# ET-IO.net
KiCad netlist of a schematic drawn in Altium Designer
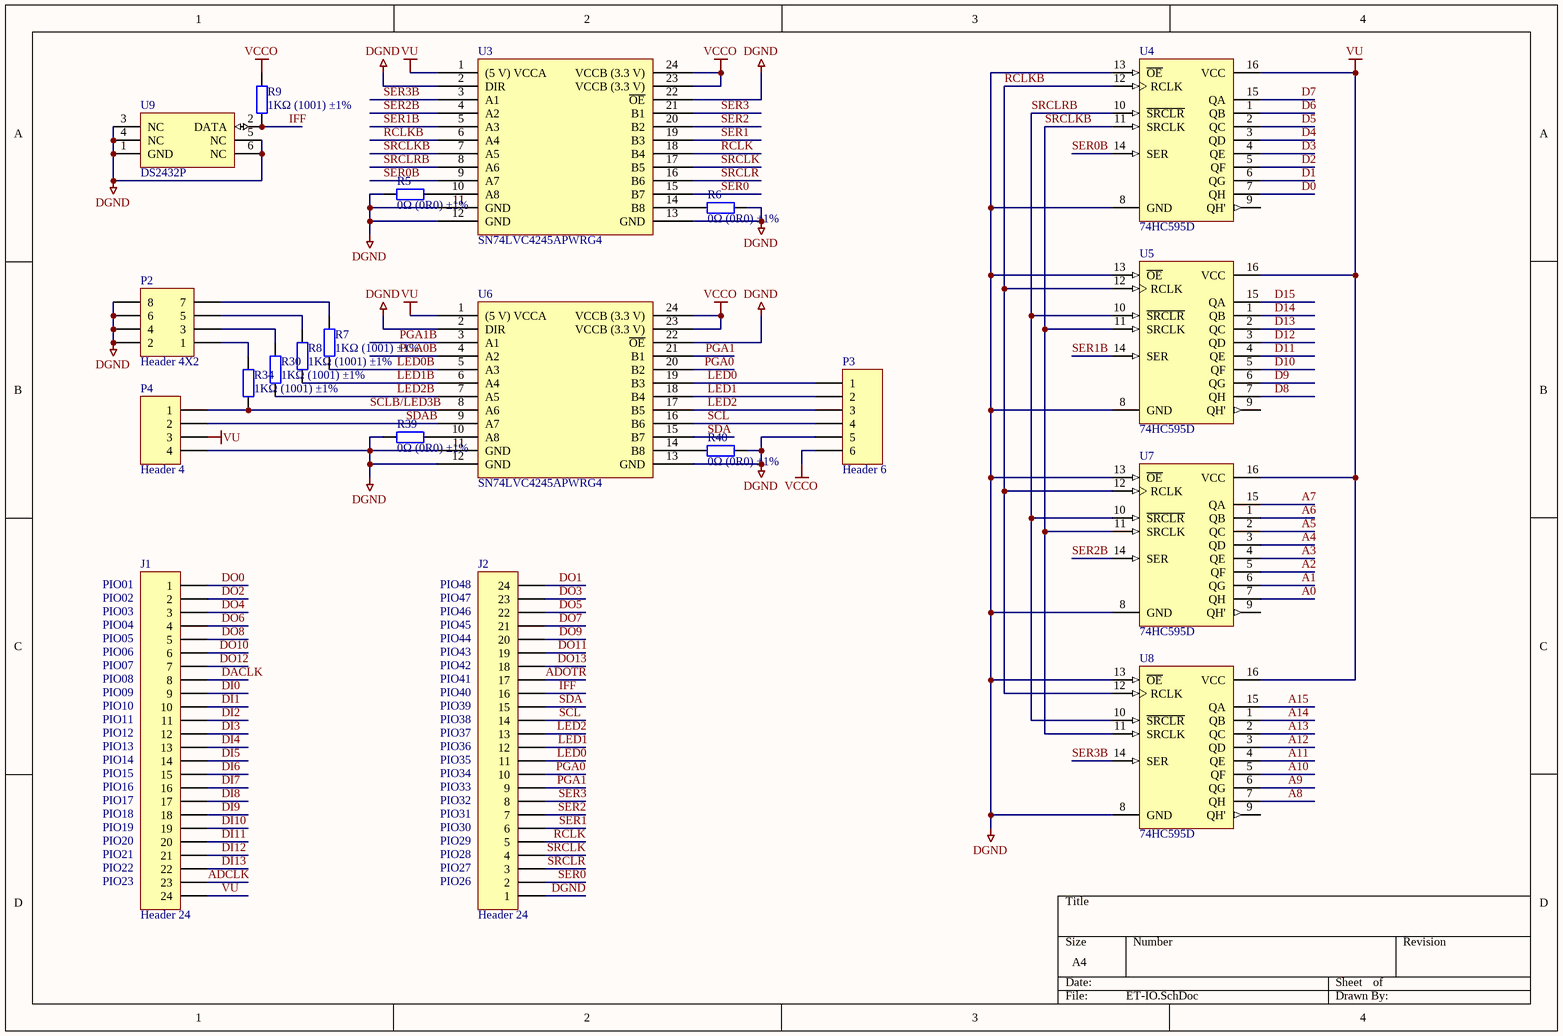
[diagram p0: ET-IO.SchDoc]

(export (version "E")
  (design (tool "Eeschema 10.0.6"))
  (components
    (comp (ref "J1")
      (value "Header 24")
      (footprint "HDR1X24")
      (description "Header, 24-Pin")
      (fields (field (name "PUBLISHER") "Altium Limited"))
      (libsource (lib "") (part "Header 24_1"))
    )
    (comp (ref "J2")
      (value "Header 24")
      (footprint "HDR1X24")
      (description "Header, 24-Pin")
      (fields (field (name "PUBLISHER") "Altium Limited"))
      (libsource (lib "Miscellaneous Connectors") (part "Header 24"))
    )
    (comp (ref "P2")
      (value "Header 4X2")
      (footprint "HDR2X4")
      (description "Header, 4-Pin, Dual row")
      (fields (field (name "PUBLISHER") "Altium Limited"))
      (libsource (lib "Miscellaneous Connectors") (part "Header 4X2"))
    )
    (comp (ref "P3")
      (value "Header 6")
      (footprint "HDR1X6")
      (description "Header, 6-Pin")
      (fields (field (name "PUBLISHER") "Altium Limited"))
      (libsource (lib "Miscellaneous Connectors") (part "Header 6"))
    )
    (comp (ref "P4")
      (value "Header 4")
      (footprint "HDR1X4")
      (description "Header, 4-Pin")
      (fields (field (name "PUBLISHER") "Altium Limited"))
      (libsource (lib "Miscellaneous Connectors") (part "Header 4"))
    )
    (comp (ref "R5")
      (value "0Ω (0R0) ±1%")
      (footprint "LC-0805_R")
      (description "贴片电阻")
      (libsource (lib "Miscellaneous Devices LC") (part "0805 0Ω (0R0) 1%"))
    )
    (comp (ref "R6")
      (value "0Ω (0R0) ±1%")
      (footprint "LC-0805_R")
      (description "贴片电阻")
      (libsource (lib "Miscellaneous Devices LC") (part "0805 0Ω (0R0) 1%"))
    )
    (comp (ref "R7")
      (value "1KΩ (1001) ±1%")
      (footprint "LC-0805_R")
      (description "贴片电阻")
      (libsource (lib "Miscellaneous Devices LC") (part "0805 1KΩ (1001) 1%"))
    )
    (comp (ref "R8")
      (value "1KΩ (1001) ±1%")
      (footprint "LC-0805_R")
      (description "贴片电阻")
      (libsource (lib "Miscellaneous Devices LC") (part "0805 1KΩ (1001) 1%"))
    )
    (comp (ref "R9")
      (value "1KΩ (1001) ±1%")
      (footprint "LC-0805_R")
      (description "贴片电阻")
      (libsource (lib "Miscellaneous Devices LC") (part "0805 1KΩ (1001) 1%"))
    )
    (comp (ref "R30")
      (value "1KΩ (1001) ±1%")
      (footprint "LC-0805_R")
      (description "贴片电阻")
      (libsource (lib "") (part "0805 1KΩ (1001) 1%_1"))
    )
    (comp (ref "R34")
      (value "1KΩ (1001) ±1%")
      (footprint "LC-0805_R")
      (description "贴片电阻")
      (libsource (lib "Miscellaneous Devices LC") (part "0805 1KΩ (1001) 1%"))
    )
    (comp (ref "R39")
      (value "0Ω (0R0) ±1%")
      (footprint "LC-0805_R")
      (description "贴片电阻")
      (libsource (lib "Miscellaneous Devices LC") (part "0805 0Ω (0R0) 1%"))
    )
    (comp (ref "R40")
      (value "0Ω (0R0) ±1%")
      (footprint "LC-0805_R")
      (description "贴片电阻")
      (libsource (lib "Miscellaneous Devices LC") (part "0805 0Ω (0R0) 1%"))
    )
    (comp (ref "U3")
      (value "SN74LVC4245APWRG4")
      (footprint "LC-TSSOP-24")
      (description "74系列逻辑芯片")
      (libsource (lib "Miscellaneous Devices LC") (part "SN74LVC4245APWRG4"))
    )
    (comp (ref "U4")
      (value "74HC595D")
      (footprint "LC-SOIC-16_150mil")
      (description "74系列逻辑芯片")
      (libsource (lib "Miscellaneous Devices LC") (part "74HC595D"))
    )
    (comp (ref "U5")
      (value "74HC595D")
      (footprint "LC-SOIC-16_150mil")
      (description "74系列逻辑芯片")
      (libsource (lib "Miscellaneous Devices LC") (part "74HC595D"))
    )
    (comp (ref "U6")
      (value "SN74LVC4245APWRG4")
      (footprint "LC-TSSOP-24")
      (description "74系列逻辑芯片")
      (libsource (lib "Miscellaneous Devices LC") (part "SN74LVC4245APWRG4"))
    )
    (comp (ref "U7")
      (value "74HC595D")
      (footprint "LC-SOIC-16_150mil")
      (description "74系列逻辑芯片")
      (libsource (lib "Miscellaneous Devices LC") (part "74HC595D"))
    )
    (comp (ref "U8")
      (value "74HC595D")
      (footprint "LC-SOIC-16_150mil")
      (description "74系列逻辑芯片")
      (libsource (lib "Miscellaneous Devices LC") (part "74HC595D"))
    )
    (comp (ref "U9")
      (value "DS2432P")
      (footprint "mini-ET:TSOC6")
      (description "256-Bit 1-Wire EEPROM")
      (fields (field (name "PUBLISHER") "Altium Limited"))
      (libsource (lib "Dallas Memory EEPROM") (part "DS2430AP"))
    )
  )
  (nets
    (net (code "1") (name "/A0") (class "Default")
      (node (ref "U7") (pin "7") (pinfunction "QH_7") (pintype "tri_state"))
    )
    (net (code "2") (name "/A1") (class "Default")
      (node (ref "U7") (pin "6") (pinfunction "QG_6") (pintype "tri_state"))
    )
    (net (code "3") (name "/A2") (class "Default")
      (node (ref "U7") (pin "5") (pinfunction "QF_5") (pintype "tri_state"))
    )
    (net (code "4") (name "/A3") (class "Default")
      (node (ref "U7") (pin "4") (pinfunction "QE_4") (pintype "tri_state"))
    )
    (net (code "5") (name "/A4") (class "Default")
      (node (ref "U7") (pin "3") (pinfunction "QD_3") (pintype "tri_state"))
    )
    (net (code "6") (name "/A5") (class "Default")
      (node (ref "U7") (pin "2") (pinfunction "QC_2") (pintype "tri_state"))
    )
    (net (code "7") (name "/A6") (class "Default")
      (node (ref "U7") (pin "1") (pinfunction "QB_1") (pintype "tri_state"))
    )
    (net (code "8") (name "/A7") (class "Default")
      (node (ref "U7") (pin "15") (pinfunction "QA_15") (pintype "tri_state"))
    )
    (net (code "9") (name "/A8") (class "Default")
      (node (ref "U8") (pin "7") (pinfunction "QH_7") (pintype "tri_state"))
    )
    (net (code "10") (name "/A9") (class "Default")
      (node (ref "U8") (pin "6") (pinfunction "QG_6") (pintype "tri_state"))
    )
    (net (code "11") (name "/A10") (class "Default")
      (node (ref "U8") (pin "5") (pinfunction "QF_5") (pintype "tri_state"))
    )
    (net (code "12") (name "/A11") (class "Default")
      (node (ref "U8") (pin "4") (pinfunction "QE_4") (pintype "tri_state"))
    )
    (net (code "13") (name "/A12") (class "Default")
      (node (ref "U8") (pin "3") (pinfunction "QD_3") (pintype "tri_state"))
    )
    (net (code "14") (name "/A13") (class "Default")
      (node (ref "U8") (pin "2") (pinfunction "QC_2") (pintype "tri_state"))
    )
    (net (code "15") (name "/A14") (class "Default")
      (node (ref "U8") (pin "1") (pinfunction "QB_1") (pintype "tri_state"))
    )
    (net (code "16") (name "/A15") (class "Default")
      (node (ref "U8") (pin "15") (pinfunction "QA_15") (pintype "tri_state"))
    )
    (net (code "17") (name "/ADCLK") (class "Default")
      (node (ref "J1") (pin "23") (pinfunction "23_23") (pintype "passive"))
    )
    (net (code "18") (name "/ADOTR") (class "Default")
      (node (ref "J2") (pin "17") (pinfunction "17_17") (pintype "passive"))
    )
    (net (code "19") (name "/D0") (class "Default")
      (node (ref "U4") (pin "7") (pinfunction "QH_7") (pintype "tri_state"))
    )
    (net (code "20") (name "/D1") (class "Default")
      (node (ref "U4") (pin "6") (pinfunction "QG_6") (pintype "tri_state"))
    )
    (net (code "21") (name "/D2") (class "Default")
      (node (ref "U4") (pin "5") (pinfunction "QF_5") (pintype "tri_state"))
    )
    (net (code "22") (name "/D3") (class "Default")
      (node (ref "U4") (pin "4") (pinfunction "QE_4") (pintype "tri_state"))
    )
    (net (code "23") (name "/D4") (class "Default")
      (node (ref "U4") (pin "3") (pinfunction "QD_3") (pintype "tri_state"))
    )
    (net (code "24") (name "/D5") (class "Default")
      (node (ref "U4") (pin "2") (pinfunction "QC_2") (pintype "tri_state"))
    )
    (net (code "25") (name "/D6") (class "Default")
      (node (ref "U4") (pin "1") (pinfunction "QB_1") (pintype "tri_state"))
    )
    (net (code "26") (name "/D7") (class "Default")
      (node (ref "U4") (pin "15") (pinfunction "QA_15") (pintype "tri_state"))
    )
    (net (code "27") (name "/D8") (class "Default")
      (node (ref "U5") (pin "7") (pinfunction "QH_7") (pintype "tri_state"))
    )
    (net (code "28") (name "/D9") (class "Default")
      (node (ref "U5") (pin "6") (pinfunction "QG_6") (pintype "tri_state"))
    )
    (net (code "29") (name "/D10") (class "Default")
      (node (ref "U5") (pin "5") (pinfunction "QF_5") (pintype "tri_state"))
    )
    (net (code "30") (name "/D11") (class "Default")
      (node (ref "U5") (pin "4") (pinfunction "QE_4") (pintype "tri_state"))
    )
    (net (code "31") (name "/D12") (class "Default")
      (node (ref "U5") (pin "3") (pinfunction "QD_3") (pintype "tri_state"))
    )
    (net (code "32") (name "/D13") (class "Default")
      (node (ref "U5") (pin "2") (pinfunction "QC_2") (pintype "tri_state"))
    )
    (net (code "33") (name "/D14") (class "Default")
      (node (ref "U5") (pin "1") (pinfunction "QB_1") (pintype "tri_state"))
    )
    (net (code "34") (name "/D15") (class "Default")
      (node (ref "U5") (pin "15") (pinfunction "QA_15") (pintype "tri_state"))
    )
    (net (code "35") (name "/DACLK") (class "Default")
      (node (ref "J1") (pin "8") (pinfunction "8_8") (pintype "passive"))
    )
    (net (code "36") (name "/DI0") (class "Default")
      (node (ref "J1") (pin "9") (pinfunction "9_9") (pintype "passive"))
    )
    (net (code "37") (name "/DI1") (class "Default")
      (node (ref "J1") (pin "10") (pinfunction "10_10") (pintype "passive"))
    )
    (net (code "38") (name "/DI2") (class "Default")
      (node (ref "J1") (pin "11") (pinfunction "11_11") (pintype "passive"))
    )
    (net (code "39") (name "/DI3") (class "Default")
      (node (ref "J1") (pin "12") (pinfunction "12_12") (pintype "passive"))
    )
    (net (code "40") (name "/DI4") (class "Default")
      (node (ref "J1") (pin "13") (pinfunction "13_13") (pintype "passive"))
    )
    (net (code "41") (name "/DI5") (class "Default")
      (node (ref "J1") (pin "14") (pinfunction "14_14") (pintype "passive"))
    )
    (net (code "42") (name "/DI6") (class "Default")
      (node (ref "J1") (pin "15") (pinfunction "15_15") (pintype "passive"))
    )
    (net (code "43") (name "/DI7") (class "Default")
      (node (ref "J1") (pin "16") (pinfunction "16_16") (pintype "passive"))
    )
    (net (code "44") (name "/DI8") (class "Default")
      (node (ref "J1") (pin "17") (pinfunction "17_17") (pintype "passive"))
    )
    (net (code "45") (name "/DI9") (class "Default")
      (node (ref "J1") (pin "18") (pinfunction "18_18") (pintype "passive"))
    )
    (net (code "46") (name "/DI10") (class "Default")
      (node (ref "J1") (pin "19") (pinfunction "19_19") (pintype "passive"))
    )
    (net (code "47") (name "/DI11") (class "Default")
      (node (ref "J1") (pin "20") (pinfunction "20_20") (pintype "passive"))
    )
    (net (code "48") (name "/DI12") (class "Default")
      (node (ref "J1") (pin "21") (pinfunction "21_21") (pintype "passive"))
    )
    (net (code "49") (name "/DI13") (class "Default")
      (node (ref "J1") (pin "22") (pinfunction "22_22") (pintype "passive"))
    )
    (net (code "50") (name "/DO0") (class "Default")
      (node (ref "J1") (pin "1") (pinfunction "1_1") (pintype "passive"))
    )
    (net (code "51") (name "/DO1") (class "Default")
      (node (ref "J2") (pin "24") (pinfunction "24_24") (pintype "passive"))
    )
    (net (code "52") (name "/DO2") (class "Default")
      (node (ref "J1") (pin "2") (pinfunction "2_2") (pintype "passive"))
    )
    (net (code "53") (name "/DO3") (class "Default")
      (node (ref "J2") (pin "23") (pinfunction "23_23") (pintype "passive"))
    )
    (net (code "54") (name "/DO4") (class "Default")
      (node (ref "J1") (pin "3") (pinfunction "3_3") (pintype "passive"))
    )
    (net (code "55") (name "/DO5") (class "Default")
      (node (ref "J2") (pin "22") (pinfunction "22_22") (pintype "passive"))
    )
    (net (code "56") (name "/DO6") (class "Default")
      (node (ref "J1") (pin "4") (pinfunction "4_4") (pintype "passive"))
    )
    (net (code "57") (name "/DO7") (class "Default")
      (node (ref "J2") (pin "21") (pinfunction "21_21") (pintype "passive"))
    )
    (net (code "58") (name "/DO8") (class "Default")
      (node (ref "J1") (pin "5") (pinfunction "5_5") (pintype "passive"))
    )
    (net (code "59") (name "/DO9") (class "Default")
      (node (ref "J2") (pin "20") (pinfunction "20_20") (pintype "passive"))
    )
    (net (code "60") (name "/DO10") (class "Default")
      (node (ref "J1") (pin "6") (pinfunction "6_6") (pintype "passive"))
    )
    (net (code "61") (name "/DO11") (class "Default")
      (node (ref "J2") (pin "19") (pinfunction "19_19") (pintype "passive"))
    )
    (net (code "62") (name "/DO12") (class "Default")
      (node (ref "J1") (pin "7") (pinfunction "7_7") (pintype "passive"))
    )
    (net (code "63") (name "/DO13") (class "Default")
      (node (ref "J2") (pin "18") (pinfunction "18_18") (pintype "passive"))
    )
    (net (code "64") (name "/IFF") (class "Default")
      (node (ref "J2") (pin "16") (pinfunction "16_16") (pintype "passive"))
      (node (ref "R9") (pin "2") (pinfunction "2_2") (pintype "passive"))
      (node (ref "U9") (pin "2") (pinfunction "DATA_2") (pintype "bidirectional"))
    )
    (net (code "65") (name "/LED0") (class "Default")
      (node (ref "J2") (pin "11") (pinfunction "11_11") (pintype "passive"))
      (node (ref "P3") (pin "1") (pinfunction "1_1") (pintype "passive"))
      (node (ref "U6") (pin "19") (pinfunction "B3_19") (pintype "passive"))
    )
    (net (code "66") (name "/LED0B") (class "Default")
      (node (ref "R7") (pin "2") (pinfunction "2_2") (pintype "passive"))
      (node (ref "U6") (pin "5") (pinfunction "A3_5") (pintype "passive"))
    )
    (net (code "67") (name "/LED1") (class "Default")
      (node (ref "J2") (pin "12") (pinfunction "12_12") (pintype "passive"))
      (node (ref "P3") (pin "2") (pinfunction "2_2") (pintype "passive"))
      (node (ref "U6") (pin "18") (pinfunction "B4_18") (pintype "passive"))
    )
    (net (code "68") (name "/LED1B") (class "Default")
      (node (ref "R8") (pin "2") (pinfunction "2_2") (pintype "passive"))
      (node (ref "U6") (pin "6") (pinfunction "A4_6") (pintype "passive"))
    )
    (net (code "69") (name "/LED2") (class "Default")
      (node (ref "J2") (pin "13") (pinfunction "13_13") (pintype "passive"))
      (node (ref "P3") (pin "3") (pinfunction "3_3") (pintype "passive"))
      (node (ref "U6") (pin "17") (pinfunction "B5_17") (pintype "passive"))
    )
    (net (code "70") (name "/LED2B") (class "Default")
      (node (ref "R30") (pin "1") (pinfunction "1_1") (pintype "passive"))
      (node (ref "U6") (pin "7") (pinfunction "A5_7") (pintype "passive"))
    )
    (net (code "71") (name "/PGA0") (class "Default")
      (node (ref "J2") (pin "10") (pinfunction "10_10") (pintype "passive"))
      (node (ref "U6") (pin "20") (pinfunction "B2_20") (pintype "passive"))
    )
    (net (code "72") (name "/PGA0B") (class "Default")
      (node (ref "U6") (pin "4") (pinfunction "A2_4") (pintype "passive"))
    )
    (net (code "73") (name "/PGA1") (class "Default")
      (node (ref "J2") (pin "9") (pinfunction "9_9") (pintype "passive"))
      (node (ref "U6") (pin "21") (pinfunction "B1_21") (pintype "passive"))
    )
    (net (code "74") (name "/PGA1B") (class "Default")
      (node (ref "U6") (pin "3") (pinfunction "A1_3") (pintype "passive"))
    )
    (net (code "75") (name "/RCLK") (class "Default")
      (node (ref "J2") (pin "5") (pinfunction "5_5") (pintype "passive"))
      (node (ref "U3") (pin "18") (pinfunction "B4_18") (pintype "passive"))
    )
    (net (code "76") (name "/RCLKB") (class "Default")
      (node (ref "U3") (pin "6") (pinfunction "A4_6") (pintype "passive"))
      (node (ref "U4") (pin "12") (pinfunction "RCLK_12") (pintype "input"))
      (node (ref "U5") (pin "12") (pinfunction "RCLK_12") (pintype "input"))
      (node (ref "U7") (pin "12") (pinfunction "RCLK_12") (pintype "input"))
      (node (ref "U8") (pin "12") (pinfunction "RCLK_12") (pintype "input"))
    )
    (net (code "77") (name "/SCL") (class "Default")
      (node (ref "J2") (pin "14") (pinfunction "14_14") (pintype "passive"))
      (node (ref "P3") (pin "4") (pinfunction "4_4") (pintype "passive"))
      (node (ref "U6") (pin "16") (pinfunction "B6_16") (pintype "passive"))
    )
    (net (code "78") (name "/SCLB{slash}LED3B") (class "Default")
      (node (ref "P4") (pin "1") (pinfunction "1_1") (pintype "passive"))
      (node (ref "R34") (pin "2") (pinfunction "2_2") (pintype "passive"))
      (node (ref "U6") (pin "8") (pinfunction "A6_8") (pintype "passive"))
    )
    (net (code "79") (name "/SDA") (class "Default")
      (node (ref "J2") (pin "15") (pinfunction "15_15") (pintype "passive"))
      (node (ref "U6") (pin "15") (pinfunction "B7_15") (pintype "passive"))
    )
    (net (code "80") (name "/SDAB") (class "Default")
      (node (ref "P4") (pin "2") (pinfunction "2_2") (pintype "passive"))
      (node (ref "U6") (pin "9") (pinfunction "A7_9") (pintype "passive"))
    )
    (net (code "81") (name "/SER0") (class "Default")
      (node (ref "J2") (pin "2") (pinfunction "2_2") (pintype "passive"))
      (node (ref "U3") (pin "15") (pinfunction "B7_15") (pintype "passive"))
    )
    (net (code "82") (name "/SER0B") (class "Default")
      (node (ref "U3") (pin "9") (pinfunction "A7_9") (pintype "passive"))
      (node (ref "U4") (pin "14") (pinfunction "SER_14") (pintype "input"))
    )
    (net (code "83") (name "/SER1") (class "Default")
      (node (ref "J2") (pin "6") (pinfunction "6_6") (pintype "passive"))
      (node (ref "U3") (pin "19") (pinfunction "B3_19") (pintype "passive"))
    )
    (net (code "84") (name "/SER1B") (class "Default")
      (node (ref "U3") (pin "5") (pinfunction "A3_5") (pintype "passive"))
      (node (ref "U5") (pin "14") (pinfunction "SER_14") (pintype "input"))
    )
    (net (code "85") (name "/SER2") (class "Default")
      (node (ref "J2") (pin "7") (pinfunction "7_7") (pintype "passive"))
      (node (ref "U3") (pin "20") (pinfunction "B2_20") (pintype "passive"))
    )
    (net (code "86") (name "/SER2B") (class "Default")
      (node (ref "U3") (pin "4") (pinfunction "A2_4") (pintype "passive"))
      (node (ref "U7") (pin "14") (pinfunction "SER_14") (pintype "input"))
    )
    (net (code "87") (name "/SER3") (class "Default")
      (node (ref "J2") (pin "8") (pinfunction "8_8") (pintype "passive"))
      (node (ref "U3") (pin "21") (pinfunction "B1_21") (pintype "passive"))
    )
    (net (code "88") (name "/SER3B") (class "Default")
      (node (ref "U3") (pin "3") (pinfunction "A1_3") (pintype "passive"))
      (node (ref "U8") (pin "14") (pinfunction "SER_14") (pintype "input"))
    )
    (net (code "89") (name "/SRCLK") (class "Default")
      (node (ref "J2") (pin "4") (pinfunction "4_4") (pintype "passive"))
      (node (ref "U3") (pin "17") (pinfunction "B5_17") (pintype "passive"))
    )
    (net (code "90") (name "/SRCLKB") (class "Default")
      (node (ref "U3") (pin "7") (pinfunction "A5_7") (pintype "passive"))
      (node (ref "U4") (pin "11") (pinfunction "SRCLK_11") (pintype "input"))
      (node (ref "U5") (pin "11") (pinfunction "SRCLK_11") (pintype "input"))
      (node (ref "U7") (pin "11") (pinfunction "SRCLK_11") (pintype "input"))
      (node (ref "U8") (pin "11") (pinfunction "SRCLK_11") (pintype "input"))
    )
    (net (code "91") (name "/SRCLR") (class "Default")
      (node (ref "J2") (pin "3") (pinfunction "3_3") (pintype "passive"))
      (node (ref "U3") (pin "16") (pinfunction "B6_16") (pintype "passive"))
    )
    (net (code "92") (name "/SRCLRB") (class "Default")
      (node (ref "U3") (pin "8") (pinfunction "A6_8") (pintype "passive"))
      (node (ref "U4") (pin "10") (pinfunction "~{SRCLR}_10") (pintype "input"))
      (node (ref "U5") (pin "10") (pinfunction "~{SRCLR}_10") (pintype "input"))
      (node (ref "U7") (pin "10") (pinfunction "~{SRCLR}_10") (pintype "input"))
      (node (ref "U8") (pin "10") (pinfunction "~{SRCLR}_10") (pintype "input"))
    )
    (net (code "93") (name "DGND") (class "Default")
      (node (ref "J2") (pin "1") (pinfunction "1_1") (pintype "passive"))
      (node (ref "P2") (pin "2") (pinfunction "2_2") (pintype "passive"))
      (node (ref "P2") (pin "4") (pinfunction "4_4") (pintype "passive"))
      (node (ref "P2") (pin "6") (pinfunction "6_6") (pintype "passive"))
      (node (ref "P2") (pin "8") (pinfunction "8_8") (pintype "passive"))
      (node (ref "P3") (pin "5") (pinfunction "5_5") (pintype "passive"))
      (node (ref "P4") (pin "4") (pinfunction "4_4") (pintype "passive"))
      (node (ref "R39") (pin "1") (pinfunction "1_1") (pintype "passive"))
      (node (ref "R40") (pin "2") (pinfunction "2_2") (pintype "passive"))
      (node (ref "R5") (pin "1") (pinfunction "1_1") (pintype "passive"))
      (node (ref "R6") (pin "2") (pinfunction "2_2") (pintype "passive"))
      (node (ref "U3") (pin "11") (pinfunction "GND_11") (pintype "passive"))
      (node (ref "U3") (pin "12") (pinfunction "GND_12") (pintype "passive"))
      (node (ref "U3") (pin "13") (pinfunction "GND_13") (pintype "passive"))
      (node (ref "U3") (pin "2") (pinfunction "DIR_2") (pintype "passive"))
      (node (ref "U3") (pin "22") (pinfunction "~{OE}_22") (pintype "passive"))
      (node (ref "U4") (pin "13") (pinfunction "~{OE}_13") (pintype "input"))
      (node (ref "U4") (pin "8") (pinfunction "GND_8") (pintype "power_in"))
      (node (ref "U5") (pin "13") (pinfunction "~{OE}_13") (pintype "input"))
      (node (ref "U5") (pin "8") (pinfunction "GND_8") (pintype "power_in"))
      (node (ref "U6") (pin "11") (pinfunction "GND_11") (pintype "passive"))
      (node (ref "U6") (pin "12") (pinfunction "GND_12") (pintype "passive"))
      (node (ref "U6") (pin "13") (pinfunction "GND_13") (pintype "passive"))
      (node (ref "U6") (pin "2") (pinfunction "DIR_2") (pintype "passive"))
      (node (ref "U6") (pin "22") (pinfunction "~{OE}_22") (pintype "passive"))
      (node (ref "U7") (pin "13") (pinfunction "~{OE}_13") (pintype "input"))
      (node (ref "U7") (pin "8") (pinfunction "GND_8") (pintype "power_in"))
      (node (ref "U8") (pin "13") (pinfunction "~{OE}_13") (pintype "input"))
      (node (ref "U8") (pin "8") (pinfunction "GND_8") (pintype "power_in"))
      (node (ref "U9") (pin "1") (pinfunction "GND_1") (pintype "power_in"))
      (node (ref "U9") (pin "3") (pinfunction "NC_3") (pintype "passive"))
      (node (ref "U9") (pin "4") (pinfunction "NC_4") (pintype "passive"))
      (node (ref "U9") (pin "5") (pinfunction "NC_5") (pintype "passive"))
      (node (ref "U9") (pin "6") (pinfunction "NC_6") (pintype "passive"))
    )
    (net (code "94") (name "Net-(P2-Pad1)") (class "Default")
      (node (ref "P2") (pin "1") (pinfunction "1_1") (pintype "passive"))
      (node (ref "R34") (pin "1") (pinfunction "1_1") (pintype "passive"))
    )
    (net (code "95") (name "Net-(P2-Pad3)") (class "Default")
      (node (ref "P2") (pin "3") (pinfunction "3_3") (pintype "passive"))
      (node (ref "R30") (pin "2") (pinfunction "2_2") (pintype "passive"))
    )
    (net (code "96") (name "Net-(P2-Pad5)") (class "Default")
      (node (ref "P2") (pin "5") (pinfunction "5_5") (pintype "passive"))
      (node (ref "R8") (pin "1") (pinfunction "1_1") (pintype "passive"))
    )
    (net (code "97") (name "Net-(P2-Pad7)") (class "Default")
      (node (ref "P2") (pin "7") (pinfunction "7_7") (pintype "passive"))
      (node (ref "R7") (pin "1") (pinfunction "1_1") (pintype "passive"))
    )
    (net (code "98") (name "Net-(U3-A8)") (class "Default")
      (node (ref "R5") (pin "2") (pinfunction "2_2") (pintype "passive"))
      (node (ref "U3") (pin "10") (pinfunction "A8_10") (pintype "passive"))
    )
    (net (code "99") (name "Net-(U3-B8)") (class "Default")
      (node (ref "R6") (pin "1") (pinfunction "1_1") (pintype "passive"))
      (node (ref "U3") (pin "14") (pinfunction "B8_14") (pintype "passive"))
    )
    (net (code "100") (name "Net-(U6-A8)") (class "Default")
      (node (ref "R39") (pin "2") (pinfunction "2_2") (pintype "passive"))
      (node (ref "U6") (pin "10") (pinfunction "A8_10") (pintype "passive"))
    )
    (net (code "101") (name "Net-(U6-B8)") (class "Default")
      (node (ref "R40") (pin "1") (pinfunction "1_1") (pintype "passive"))
      (node (ref "U6") (pin "14") (pinfunction "B8_14") (pintype "passive"))
    )
    (net (code "102") (name "VCCO") (class "Default")
      (node (ref "P3") (pin "6") (pinfunction "6_6") (pintype "passive"))
      (node (ref "R9") (pin "1") (pinfunction "1_1") (pintype "passive"))
      (node (ref "U3") (pin "23") (pinfunction "VCCB_(3.3_V)_23") (pintype "passive"))
      (node (ref "U3") (pin "24") (pinfunction "VCCB_(3.3_V)_24") (pintype "passive"))
      (node (ref "U6") (pin "23") (pinfunction "VCCB_(3.3_V)_23") (pintype "passive"))
      (node (ref "U6") (pin "24") (pinfunction "VCCB_(3.3_V)_24") (pintype "passive"))
    )
    (net (code "103") (name "VU") (class "Default")
      (node (ref "J1") (pin "24") (pinfunction "24_24") (pintype "passive"))
      (node (ref "P4") (pin "3") (pinfunction "3_3") (pintype "passive"))
      (node (ref "U3") (pin "1") (pinfunction "(5_V)_VCCA_1") (pintype "passive"))
      (node (ref "U4") (pin "16") (pinfunction "VCC_16") (pintype "power_in"))
      (node (ref "U5") (pin "16") (pinfunction "VCC_16") (pintype "power_in"))
      (node (ref "U6") (pin "1") (pinfunction "(5_V)_VCCA_1") (pintype "passive"))
      (node (ref "U7") (pin "16") (pinfunction "VCC_16") (pintype "power_in"))
      (node (ref "U8") (pin "16") (pinfunction "VCC_16") (pintype "power_in"))
    )
    (net (code "104") (name "unconnected-(U4-QH'-Pad9)") (class "Default")
      (node (ref "U4") (pin "9") (pinfunction "QH'_9") (pintype "output"))
    )
    (net (code "105") (name "unconnected-(U5-QH'-Pad9)") (class "Default")
      (node (ref "U5") (pin "9") (pinfunction "QH'_9") (pintype "output"))
    )
    (net (code "106") (name "unconnected-(U7-QH'-Pad9)") (class "Default")
      (node (ref "U7") (pin "9") (pinfunction "QH'_9") (pintype "output"))
    )
    (net (code "107") (name "unconnected-(U8-QH'-Pad9)") (class "Default")
      (node (ref "U8") (pin "9") (pinfunction "QH'_9") (pintype "output"))
    )
  )
)
